# hvac-sensors-v3.net
KiCad netlist of a schematic drawn in EAGLE
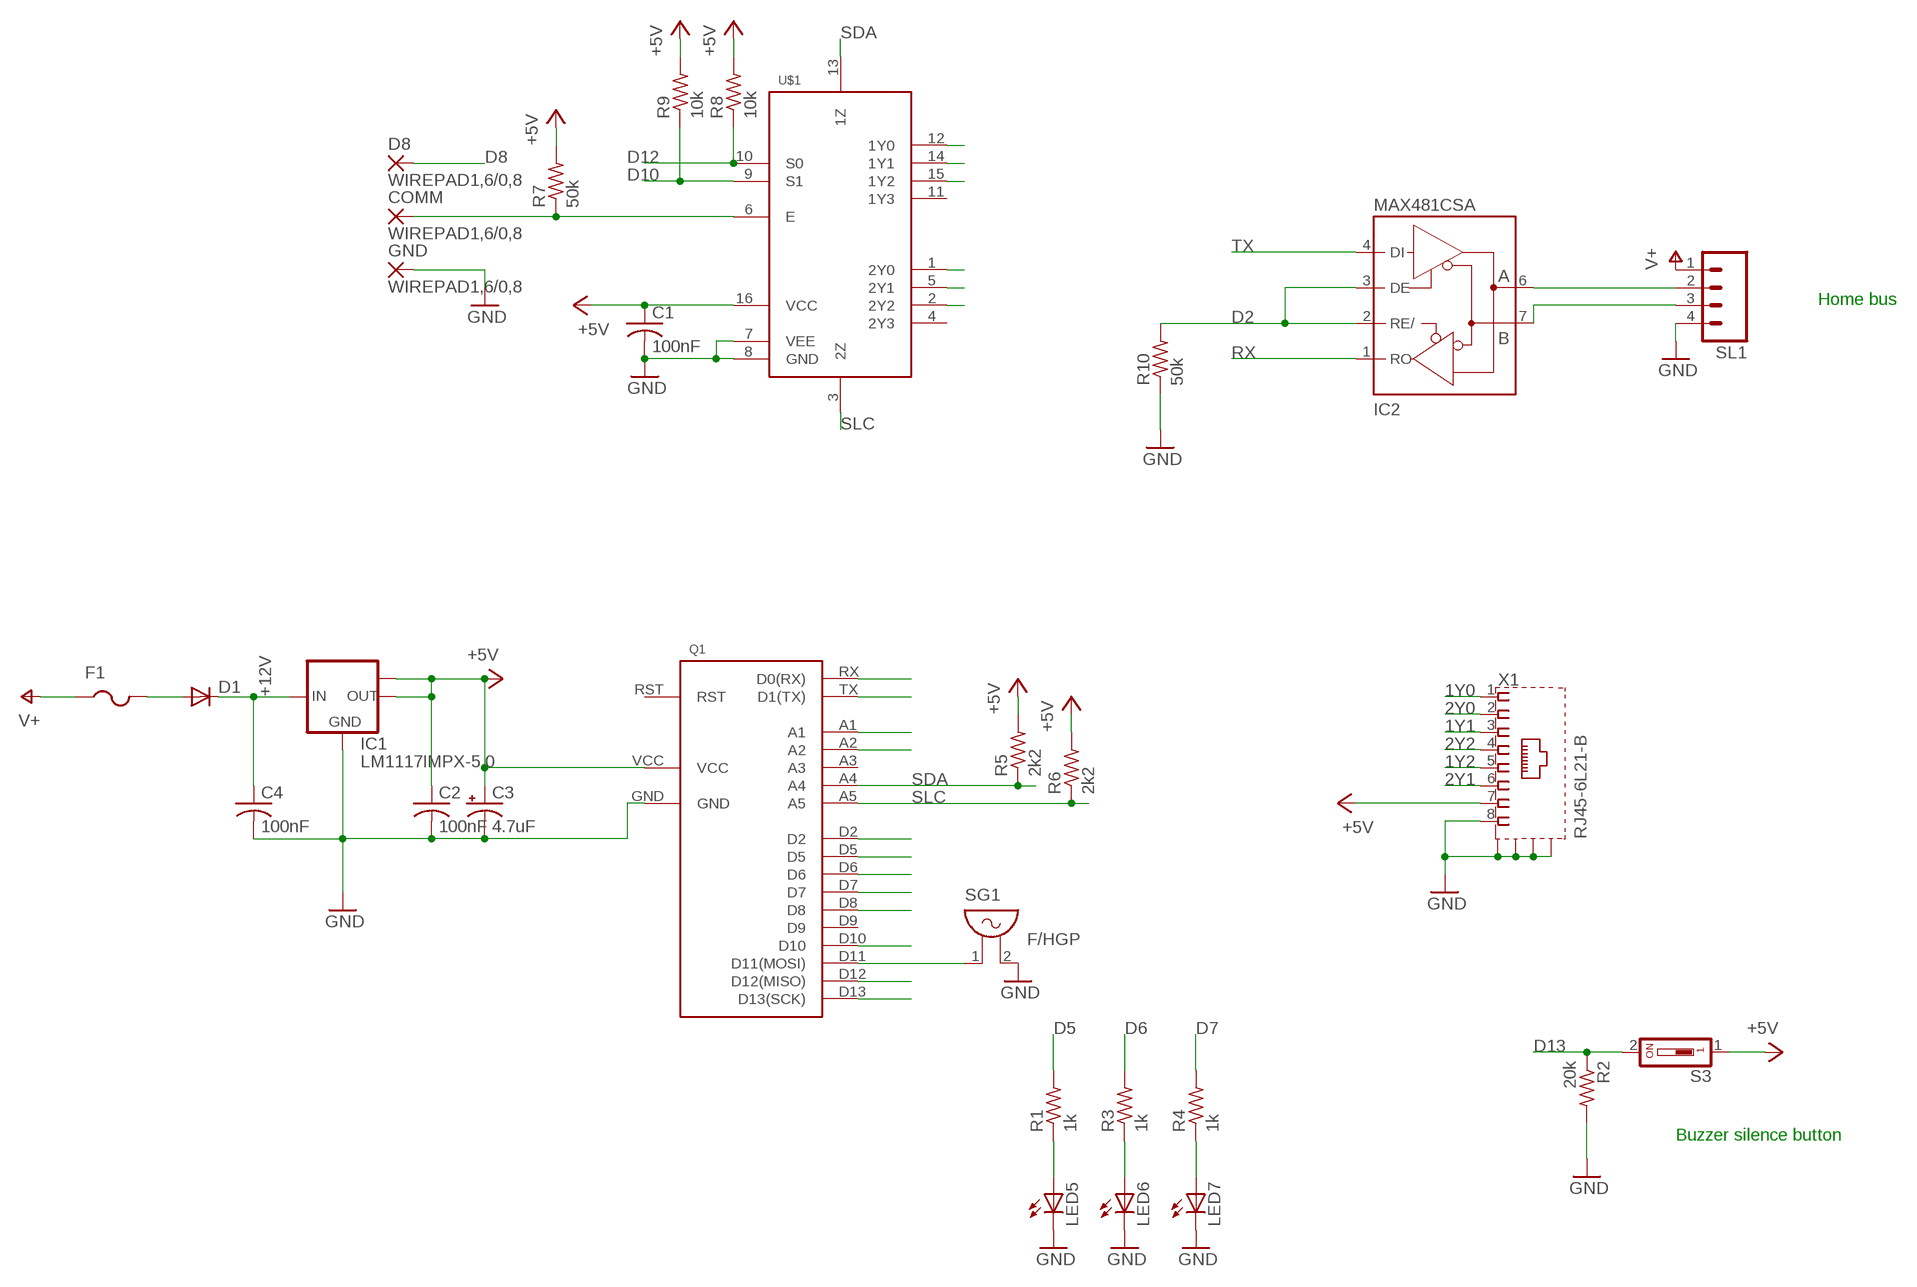
[diagram p0: schematic, sheet 1]

(export (version "E")
  (design (tool "Eeschema 10.0.6"))
  (components
    (comp (ref "C1")
      (value "100nF")
      (footprint "eagle-import:C0603K")
      (libsource (lib "eagle-import") (part "C-USC0603K"))
    )
    (comp (ref "C2")
      (value "100nF")
      (footprint "eagle-import:C0603K")
      (libsource (lib "eagle-import") (part "C-USC0603K"))
    )
    (comp (ref "C3")
      (value "4.7uF")
      (footprint "eagle-import:E1,8-4")
      (libsource (lib "eagle-import") (part "CPOL-USE1.8-4"))
    )
    (comp (ref "C4")
      (value "100nF")
      (footprint "eagle-import:C0603K")
      (libsource (lib "eagle-import") (part "C-USC0603K"))
    )
    (comp (ref "COMM")
      (value "WIREPAD1,6/0,8")
      (footprint "eagle-import:1,6_0,8")
      (libsource (lib "eagle-import") (part "WIREPAD1,6/0,8"))
    )
    (comp (ref "D1")
      (value "DIODE-MICROMELF-W")
      (footprint "eagle-import:MICROMELF-W")
      (libsource (lib "eagle-import") (part "DIODE-MICROMELF-W"))
    )
    (comp (ref "D8")
      (value "WIREPAD1,6/0,8")
      (footprint "eagle-import:1,6_0,8")
      (libsource (lib "eagle-import") (part "WIREPAD1,6/0,8"))
    )
    (comp (ref "F1")
      (value "PTCFUSE-1812")
      (footprint "eagle-import:1812")
      (libsource (lib "eagle-import") (part "PTCFUSE-1812"))
    )
    (comp (ref "GND")
      (value "WIREPAD1,6/0,8")
      (footprint "eagle-import:1,6_0,8")
      (libsource (lib "eagle-import") (part "WIREPAD1,6/0,8"))
    )
    (comp (ref "IC1")
      (value "LM1117IMPX-5.0")
      (footprint "eagle-import:SOT223")
      (libsource (lib "eagle-import") (part "LM1117IMPX-5.0"))
    )
    (comp (ref "IC2")
      (value "MAX481CSA")
      (footprint "eagle-import:SO08")
      (fields (field (name "MF") "MAXIM"))
      (libsource (lib "eagle-import") (part "MAX481CSA"))
    )
    (comp (ref "LED5")
      (value "LED5MM")
      (footprint "eagle-import:LED5MM")
      (libsource (lib "eagle-import") (part "LED5MM"))
    )
    (comp (ref "LED6")
      (value "LED5MM")
      (footprint "eagle-import:LED5MM")
      (libsource (lib "eagle-import") (part "LED5MM"))
    )
    (comp (ref "LED7")
      (value "LED5MM")
      (footprint "eagle-import:LED5MM")
      (libsource (lib "eagle-import") (part "LED5MM"))
    )
    (comp (ref "Q1")
      (value "HOME-CPU-V1")
      (footprint "eagle-import:HOME-CPU-V1")
      (libsource (lib "eagle-import") (part "HOME-CPU-V1"))
    )
    (comp (ref "R1")
      (value "1k")
      (footprint "eagle-import:R0603")
      (libsource (lib "eagle-import") (part "R-US_R0603"))
    )
    (comp (ref "R2")
      (value "20k")
      (footprint "eagle-import:R0603")
      (libsource (lib "eagle-import") (part "R-US_R0603"))
    )
    (comp (ref "R3")
      (value "1k")
      (footprint "eagle-import:R0603")
      (libsource (lib "eagle-import") (part "R-US_R0603"))
    )
    (comp (ref "R4")
      (value "1k")
      (footprint "eagle-import:R0603")
      (libsource (lib "eagle-import") (part "R-US_R0603"))
    )
    (comp (ref "R5")
      (value "2k2")
      (footprint "eagle-import:R0603")
      (libsource (lib "eagle-import") (part "R-US_R0603"))
    )
    (comp (ref "R6")
      (value "2k2")
      (footprint "eagle-import:R0603")
      (libsource (lib "eagle-import") (part "R-US_R0603"))
    )
    (comp (ref "R7")
      (value "50k")
      (footprint "eagle-import:R0603")
      (libsource (lib "eagle-import") (part "R-US_R0603"))
    )
    (comp (ref "R8")
      (value "10k")
      (footprint "eagle-import:R0603")
      (libsource (lib "eagle-import") (part "R-US_R0603"))
    )
    (comp (ref "R9")
      (value "10k")
      (footprint "eagle-import:R0603")
      (libsource (lib "eagle-import") (part "R-US_R0603"))
    )
    (comp (ref "R10")
      (value "50k")
      (footprint "eagle-import:R0603")
      (libsource (lib "eagle-import") (part "R-US_R0603"))
    )
    (comp (ref "S3")
      (value "DS01")
      (footprint "eagle-import:DS-01")
      (libsource (lib "eagle-import") (part "DS01"))
    )
    (comp (ref "SG1")
      (value "F/HGP")
      (footprint "eagle-import:F_HGP")
      (libsource (lib "eagle-import") (part "F/HGP"))
    )
    (comp (ref "SL1")
      (value "M04")
      (footprint "eagle-import:04P")
      (libsource (lib "eagle-import") (part "M04"))
    )
    (comp (ref "U$1")
      (value "74HC4052SO-16")
      (footprint "eagle-import:SO16")
      (libsource (lib "eagle-import") (part "74HC4052SO-16"))
    )
    (comp (ref "X1")
      (value "RJ45-6L21-B")
      (footprint "eagle-import:RJ45-SHIELD1")
      (libsource (lib "eagle-import") (part "RJ4521-B-6L"))
    )
  )
  (nets
    (net (code "1") (name "+5V") (class "Default")
      (node (ref "C1") (pin "1") (pinfunction "1_1") (pintype "passive"))
      (node (ref "C2") (pin "1") (pinfunction "1_1") (pintype "passive"))
      (node (ref "C3") (pin "+") (pinfunction "+_+") (pintype "passive"))
      (node (ref "IC1") (pin "2") (pinfunction "OUT_2") (pintype "passive"))
      (node (ref "IC1") (pin "TAB") (pinfunction "OUT1_TAB") (pintype "passive"))
      (node (ref "Q1") (pin "VCC") (pinfunction "VCC_VCC") (pintype "power_in"))
      (node (ref "R5") (pin "2") (pinfunction "2_2") (pintype "passive"))
      (node (ref "R6") (pin "2") (pinfunction "2_2") (pintype "passive"))
      (node (ref "R7") (pin "2") (pinfunction "2_2") (pintype "passive"))
      (node (ref "R8") (pin "2") (pinfunction "2_2") (pintype "passive"))
      (node (ref "R9") (pin "2") (pinfunction "2_2") (pintype "passive"))
      (node (ref "S3") (pin "1") (pinfunction "1_1") (pintype "passive"))
      (node (ref "U$1") (pin "16") (pinfunction "VCC_16") (pintype "power_in"))
      (node (ref "X1") (pin "7") (pinfunction "7_7") (pintype "passive"))
    )
    (net (code "2") (name "/+12V") (class "Default")
      (node (ref "C4") (pin "1") (pinfunction "1_1") (pintype "passive"))
      (node (ref "D1") (pin "C") (pinfunction "C_C") (pintype "passive"))
      (node (ref "IC1") (pin "3") (pinfunction "IN_3") (pintype "input"))
    )
    (net (code "3") (name "/1Y0") (class "Default")
      (node (ref "U$1") (pin "12") (pinfunction "1Y0_12") (pintype "bidirectional"))
      (node (ref "X1") (pin "1") (pinfunction "1_1") (pintype "passive"))
    )
    (net (code "4") (name "/1Y1") (class "Default")
      (node (ref "U$1") (pin "14") (pinfunction "1Y1_14") (pintype "bidirectional"))
      (node (ref "X1") (pin "3") (pinfunction "3_3") (pintype "passive"))
    )
    (net (code "5") (name "/1Y2") (class "Default")
      (node (ref "U$1") (pin "15") (pinfunction "1Y2_15") (pintype "bidirectional"))
      (node (ref "X1") (pin "5") (pinfunction "5_5") (pintype "passive"))
    )
    (net (code "6") (name "/2Y0") (class "Default")
      (node (ref "U$1") (pin "1") (pinfunction "2Y0_1") (pintype "bidirectional"))
      (node (ref "X1") (pin "2") (pinfunction "2_2") (pintype "passive"))
    )
    (net (code "7") (name "/2Y1") (class "Default")
      (node (ref "U$1") (pin "5") (pinfunction "2Y1_5") (pintype "bidirectional"))
      (node (ref "X1") (pin "6") (pinfunction "6_6") (pintype "passive"))
    )
    (net (code "8") (name "/2Y2") (class "Default")
      (node (ref "U$1") (pin "2") (pinfunction "2Y2_2") (pintype "bidirectional"))
      (node (ref "X1") (pin "4") (pinfunction "4_4") (pintype "passive"))
    )
    (net (code "9") (name "/D2") (class "Default")
      (node (ref "IC2") (pin "2") (pinfunction "RE/_2") (pintype "input"))
      (node (ref "IC2") (pin "3") (pinfunction "DE_3") (pintype "input"))
      (node (ref "Q1") (pin "D2") (pinfunction "D2_D2") (pintype "bidirectional"))
      (node (ref "R10") (pin "2") (pinfunction "2_2") (pintype "passive"))
    )
    (net (code "10") (name "/D5") (class "Default")
      (node (ref "Q1") (pin "D5") (pinfunction "D5_D5") (pintype "bidirectional"))
      (node (ref "R1") (pin "2") (pinfunction "2_2") (pintype "passive"))
    )
    (net (code "11") (name "/D6") (class "Default")
      (node (ref "Q1") (pin "D6") (pinfunction "D6_D6") (pintype "bidirectional"))
      (node (ref "R3") (pin "2") (pinfunction "2_2") (pintype "passive"))
    )
    (net (code "12") (name "/D7") (class "Default")
      (node (ref "Q1") (pin "D7") (pinfunction "D7_D7") (pintype "bidirectional"))
      (node (ref "R4") (pin "2") (pinfunction "2_2") (pintype "passive"))
    )
    (net (code "13") (name "/D8") (class "Default")
      (node (ref "D8") (pin "1") (pinfunction "P_1") (pintype "passive"))
      (node (ref "Q1") (pin "D8") (pinfunction "D8_D8") (pintype "bidirectional"))
    )
    (net (code "14") (name "/D10") (class "Default")
      (node (ref "Q1") (pin "D10") (pinfunction "D10_D10") (pintype "bidirectional"))
      (node (ref "R9") (pin "1") (pinfunction "1_1") (pintype "passive"))
      (node (ref "U$1") (pin "9") (pinfunction "S1_9") (pintype "bidirectional"))
    )
    (net (code "15") (name "/D12") (class "Default")
      (node (ref "Q1") (pin "D12") (pinfunction "D12(MISO)_D12") (pintype "bidirectional"))
      (node (ref "R8") (pin "1") (pinfunction "1_1") (pintype "passive"))
      (node (ref "U$1") (pin "10") (pinfunction "S0_10") (pintype "bidirectional"))
    )
    (net (code "16") (name "/D13") (class "Default")
      (node (ref "Q1") (pin "D13") (pinfunction "D13(SCK)_D13") (pintype "bidirectional"))
      (node (ref "R2") (pin "1") (pinfunction "1_1") (pintype "passive"))
      (node (ref "S3") (pin "2") (pinfunction "2_2") (pintype "passive"))
    )
    (net (code "17") (name "/RX") (class "Default")
      (node (ref "IC2") (pin "1") (pinfunction "RO_1") (pintype "output"))
      (node (ref "Q1") (pin "RX") (pinfunction "D0(RX)_RX") (pintype "input"))
    )
    (net (code "18") (name "/SDA") (class "Default")
      (node (ref "Q1") (pin "A4") (pinfunction "A4_A4") (pintype "bidirectional"))
      (node (ref "R5") (pin "1") (pinfunction "1_1") (pintype "passive"))
      (node (ref "U$1") (pin "13") (pinfunction "1Z_13") (pintype "input"))
    )
    (net (code "19") (name "/SLC") (class "Default")
      (node (ref "Q1") (pin "A5") (pinfunction "A5_A5") (pintype "bidirectional"))
      (node (ref "R6") (pin "1") (pinfunction "1_1") (pintype "passive"))
      (node (ref "U$1") (pin "3") (pinfunction "2Z_3") (pintype "output"))
    )
    (net (code "20") (name "/TX") (class "Default")
      (node (ref "IC2") (pin "4") (pinfunction "DI_4") (pintype "input"))
      (node (ref "Q1") (pin "TX") (pinfunction "D1(TX)_TX") (pintype "output"))
    )
    (net (code "21") (name "GND") (class "Default")
      (node (ref "C1") (pin "2") (pinfunction "2_2") (pintype "passive"))
      (node (ref "C2") (pin "2") (pinfunction "2_2") (pintype "passive"))
      (node (ref "C3") (pin "-") (pinfunction "-_-") (pintype "passive"))
      (node (ref "C4") (pin "2") (pinfunction "2_2") (pintype "passive"))
      (node (ref "GND") (pin "1") (pinfunction "P_1") (pintype "passive"))
      (node (ref "IC1") (pin "1") (pinfunction "GND_1") (pintype "input"))
      (node (ref "LED5") (pin "K") (pinfunction "C_K") (pintype "passive"))
      (node (ref "LED6") (pin "K") (pinfunction "C_K") (pintype "passive"))
      (node (ref "LED7") (pin "K") (pinfunction "C_K") (pintype "passive"))
      (node (ref "Q1") (pin "GND") (pinfunction "GND_GND") (pintype "power_in"))
      (node (ref "R10") (pin "1") (pinfunction "1_1") (pintype "passive"))
      (node (ref "R2") (pin "2") (pinfunction "2_2") (pintype "passive"))
      (node (ref "SG1") (pin "2") (pinfunction "2_2") (pintype "passive"))
      (node (ref "SL1") (pin "4") (pinfunction "4_4") (pintype "passive"))
      (node (ref "U$1") (pin "7") (pinfunction "VEE_7") (pintype "power_in"))
      (node (ref "U$1") (pin "8") (pinfunction "GND_8") (pintype "power_in"))
      (node (ref "X1") (pin "8") (pinfunction "8_8") (pintype "passive"))
      (node (ref "X1") (pin "S1") (pinfunction "S_S1") (pintype "passive"))
      (node (ref "X1") (pin "S2") (pinfunction "S_S2") (pintype "passive"))
      (node (ref "X1") (pin "S3") (pinfunction "S_S3") (pintype "passive"))
      (node (ref "X1") (pin "S4") (pinfunction "S_S4") (pintype "passive"))
    )
    (net (code "22") (name "Net-(COMM-P)") (class "Default")
      (node (ref "COMM") (pin "1") (pinfunction "P_1") (pintype "passive"))
      (node (ref "R7") (pin "1") (pinfunction "1_1") (pintype "passive"))
      (node (ref "U$1") (pin "6") (pinfunction "E_6") (pintype "bidirectional"))
    )
    (net (code "23") (name "Net-(D1-PadA)") (class "Default")
      (node (ref "D1") (pin "A") (pinfunction "A_A") (pintype "passive"))
      (node (ref "F1") (pin "2") (pinfunction "2_2") (pintype "passive"))
    )
    (net (code "24") (name "Net-(IC2A-A)") (class "Default")
      (node (ref "IC2") (pin "6") (pinfunction "A_6") (pintype "passive"))
      (node (ref "SL1") (pin "2") (pinfunction "2_2") (pintype "passive"))
    )
    (net (code "25") (name "Net-(IC2A-B)") (class "Default")
      (node (ref "IC2") (pin "7") (pinfunction "B_7") (pintype "passive"))
      (node (ref "SL1") (pin "3") (pinfunction "3_3") (pintype "passive"))
    )
    (net (code "26") (name "Net-(LED5-PadA)") (class "Default")
      (node (ref "LED5") (pin "A") (pinfunction "A_A") (pintype "passive"))
      (node (ref "R1") (pin "1") (pinfunction "1_1") (pintype "passive"))
    )
    (net (code "27") (name "Net-(LED6-PadA)") (class "Default")
      (node (ref "LED6") (pin "A") (pinfunction "A_A") (pintype "passive"))
      (node (ref "R3") (pin "1") (pinfunction "1_1") (pintype "passive"))
    )
    (net (code "28") (name "Net-(LED7-PadA)") (class "Default")
      (node (ref "LED7") (pin "A") (pinfunction "A_A") (pintype "passive"))
      (node (ref "R4") (pin "1") (pinfunction "1_1") (pintype "passive"))
    )
    (net (code "29") (name "Net-(Q1-D11(MOSI))") (class "Default")
      (node (ref "Q1") (pin "D11") (pinfunction "D11(MOSI)_D11") (pintype "bidirectional"))
      (node (ref "SG1") (pin "1") (pinfunction "1_1") (pintype "passive"))
    )
    (net (code "30") (name "V+") (class "Default")
      (node (ref "F1") (pin "1") (pinfunction "1_1") (pintype "passive"))
      (node (ref "SL1") (pin "1") (pinfunction "1_1") (pintype "passive"))
    )
    (net (code "31") (name "unconnected-(Q1-PadA1)") (class "Default")
      (node (ref "Q1") (pin "A1") (pinfunction "A1_A1") (pintype "bidirectional"))
    )
    (net (code "32") (name "unconnected-(Q1-PadA2)") (class "Default")
      (node (ref "Q1") (pin "A2") (pinfunction "A2_A2") (pintype "bidirectional"))
    )
    (net (code "33") (name "unconnected-(Q1-PadA3)") (class "Default")
      (node (ref "Q1") (pin "A3") (pinfunction "A3_A3") (pintype "bidirectional"))
    )
    (net (code "34") (name "unconnected-(Q1-PadD9)") (class "Default")
      (node (ref "Q1") (pin "D9") (pinfunction "D9_D9") (pintype "bidirectional"))
    )
    (net (code "35") (name "unconnected-(Q1-PadRST)") (class "Default")
      (node (ref "Q1") (pin "RST") (pinfunction "RST_RST") (pintype "passive"))
    )
    (net (code "36") (name "unconnected-(U$1-1Y3-Pad11)") (class "Default")
      (node (ref "U$1") (pin "11") (pinfunction "1Y3_11") (pintype "bidirectional"))
    )
    (net (code "37") (name "unconnected-(U$1-2Y3-Pad4)") (class "Default")
      (node (ref "U$1") (pin "4") (pinfunction "2Y3_4") (pintype "bidirectional"))
    )
  )
)
